# 7-Encodeurs.net
KiCad netlist of a schematic drawn in Altium Designer
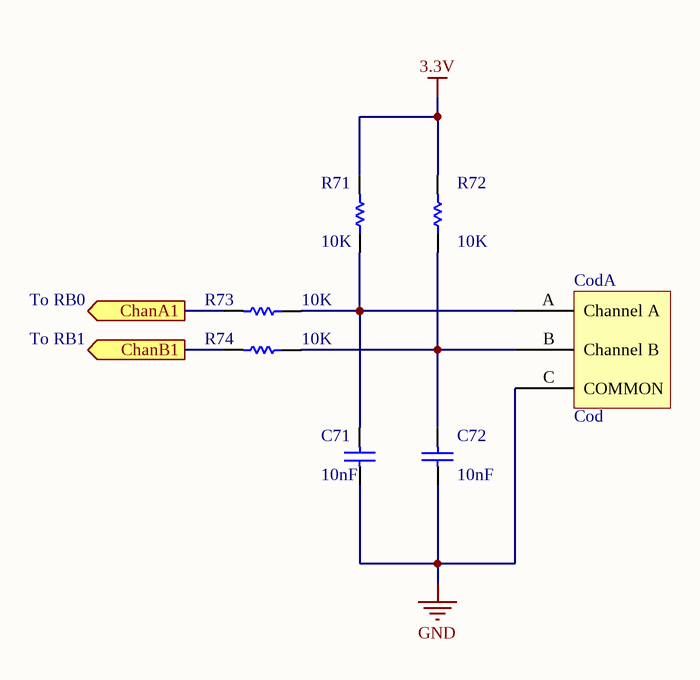
[diagram p0: 7-Encodeurs.SchDoc]

(export (version "E")
  (design (tool "Eeschema 10.0.6"))
  (components
    (comp (ref "C71")
      (value "10nF")
      (footprint "capa 1206")
      (description "Capacitor")
      (libsource (lib "Miscellaneous Devices") (part "Cap"))
    )
    (comp (ref "C72")
      (value "10nF")
      (footprint "capa 1206")
      (description "Capacitor")
      (libsource (lib "Miscellaneous Devices") (part "Cap"))
    )
    (comp (ref "Cod") (value "Cod") (libsource (lib "0x2a002a") (part "Cod")))
    (comp (ref "R71")
      (value "10K")
      (footprint "RES 1206")
      (description "Resistor")
      (libsource (lib "Miscellaneous Devices") (part "Res1"))
    )
    (comp (ref "R72")
      (value "10K")
      (footprint "RES 1206")
      (description "Resistor")
      (libsource (lib "Miscellaneous Devices") (part "Res1"))
    )
    (comp (ref "R73")
      (value "10K")
      (footprint "RES 1206")
      (description "Resistor")
      (libsource (lib "Miscellaneous Devices") (part "Res1"))
    )
    (comp (ref "R74")
      (value "10K")
      (footprint "RES 1206")
      (description "Resistor")
      (libsource (lib "Miscellaneous Devices") (part "Res1"))
    )
  )
  (nets
    (net (code "1") (name "/ChanA1") (class "Default")
      (node (ref "R73") (pin "2") (pinfunction "2_2") (pintype "passive"))
    )
    (net (code "2") (name "/ChanB1") (class "Default")
      (node (ref "R74") (pin "2") (pinfunction "2_2") (pintype "passive"))
    )
    (net (code "3") (name "3.3V") (class "Default")
      (node (ref "R71") (pin "2") (pinfunction "2_2") (pintype "passive"))
      (node (ref "R72") (pin "2") (pinfunction "2_2") (pintype "passive"))
    )
    (net (code "4") (name "GND") (class "Default")
      (node (ref "C71") (pin "1") (pinfunction "1_1") (pintype "passive"))
      (node (ref "C72") (pin "2") (pinfunction "2_2") (pintype "passive"))
      (node (ref "Cod") (pin "C") (pinfunction "COMMON_C") (pintype "power_in"))
    )
    (net (code "5") (name "Net-(CodA-Channel_A)") (class "Default")
      (node (ref "C71") (pin "2") (pinfunction "2_2") (pintype "passive"))
      (node (ref "Cod") (pin "A") (pinfunction "Channel_A_A") (pintype "passive"))
      (node (ref "R71") (pin "1") (pinfunction "1_1") (pintype "passive"))
      (node (ref "R73") (pin "1") (pinfunction "1_1") (pintype "passive"))
    )
    (net (code "6") (name "Net-(CodA-Channel_B)") (class "Default")
      (node (ref "C72") (pin "1") (pinfunction "1_1") (pintype "passive"))
      (node (ref "Cod") (pin "B") (pinfunction "Channel_B_B") (pintype "passive"))
      (node (ref "R72") (pin "1") (pinfunction "1_1") (pintype "passive"))
      (node (ref "R74") (pin "1") (pinfunction "1_1") (pintype "passive"))
    )
  )
)
